# 5_spi_memory.net
KiCad netlist of a schematic drawn in Altium Designer
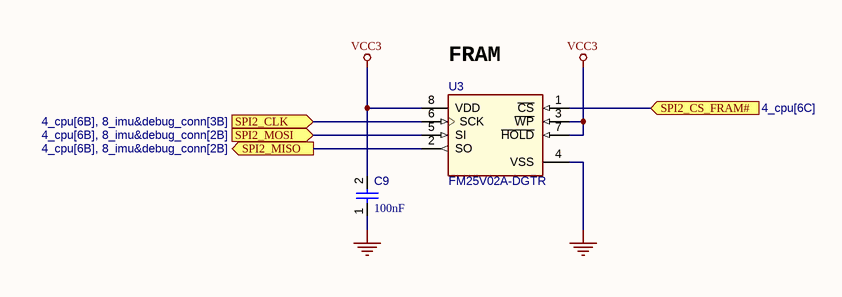
[diagram p0: 5_spi_memory.SchDoc]

(export (version "E")
  (design (tool "Eeschema 10.0.6"))
  (components
    (comp (ref "C9")
      (value "100nF")
      (footprint "CAPC0402(1005)60_L")
      (description "Chip Capacitor, 100nF +/-20%, 10V, 0402, Thickness 0.6 mm")
      (fields (field (name "TOLERANCE") "20%") (field (name "Comment") "Capacitor 100nF +/-20% 10V 0402"))
      (libsource (lib "SKA- Automa玢o de Engenharias") (part "CAP-NP-2"))
    )
    (comp (ref "U3")
      (value "FM25V02A-DGTR")
      (footprint "SON95P400X75_HS-9N")
      (description "REEL / F-RAM Memory Serial")
      (libsource (lib "<Company> Server") (part "CMP-019-00000-4"))
    )
  )
  (nets
    (net (code "1") (name "/SPI2_CLK") (class "Default")
      (node (ref "U3") (pin "6") (pinfunction "SCK_6") (pintype "input"))
    )
    (net (code "2") (name "/SPI2_CS_FRAM#") (class "Default")
      (node (ref "U3") (pin "1") (pinfunction "~{CS}_1") (pintype "input"))
    )
    (net (code "3") (name "/SPI2_MISO") (class "Default")
      (node (ref "U3") (pin "2") (pinfunction "SO_2") (pintype "output"))
    )
    (net (code "4") (name "/SPI2_MOSI") (class "Default")
      (node (ref "U3") (pin "5") (pinfunction "SI_5") (pintype "input"))
    )
    (net (code "5") (name "GND") (class "Default")
      (node (ref "C9") (pin "1") (pinfunction "1_1") (pintype "passive"))
      (node (ref "U3") (pin "4") (pinfunction "VSS_4") (pintype "power_in"))
    )
    (net (code "6") (name "VCC3") (class "Default")
      (node (ref "C9") (pin "2") (pinfunction "2_2") (pintype "passive"))
      (node (ref "U3") (pin "3") (pinfunction "~{WP}_3") (pintype "input"))
      (node (ref "U3") (pin "7") (pinfunction "~{HOLD}_7") (pintype "input"))
      (node (ref "U3") (pin "8") (pinfunction "VDD_8") (pintype "power_in"))
    )
  )
)
